# schema.net
KiCad netlist of a schematic drawn in EAGLE
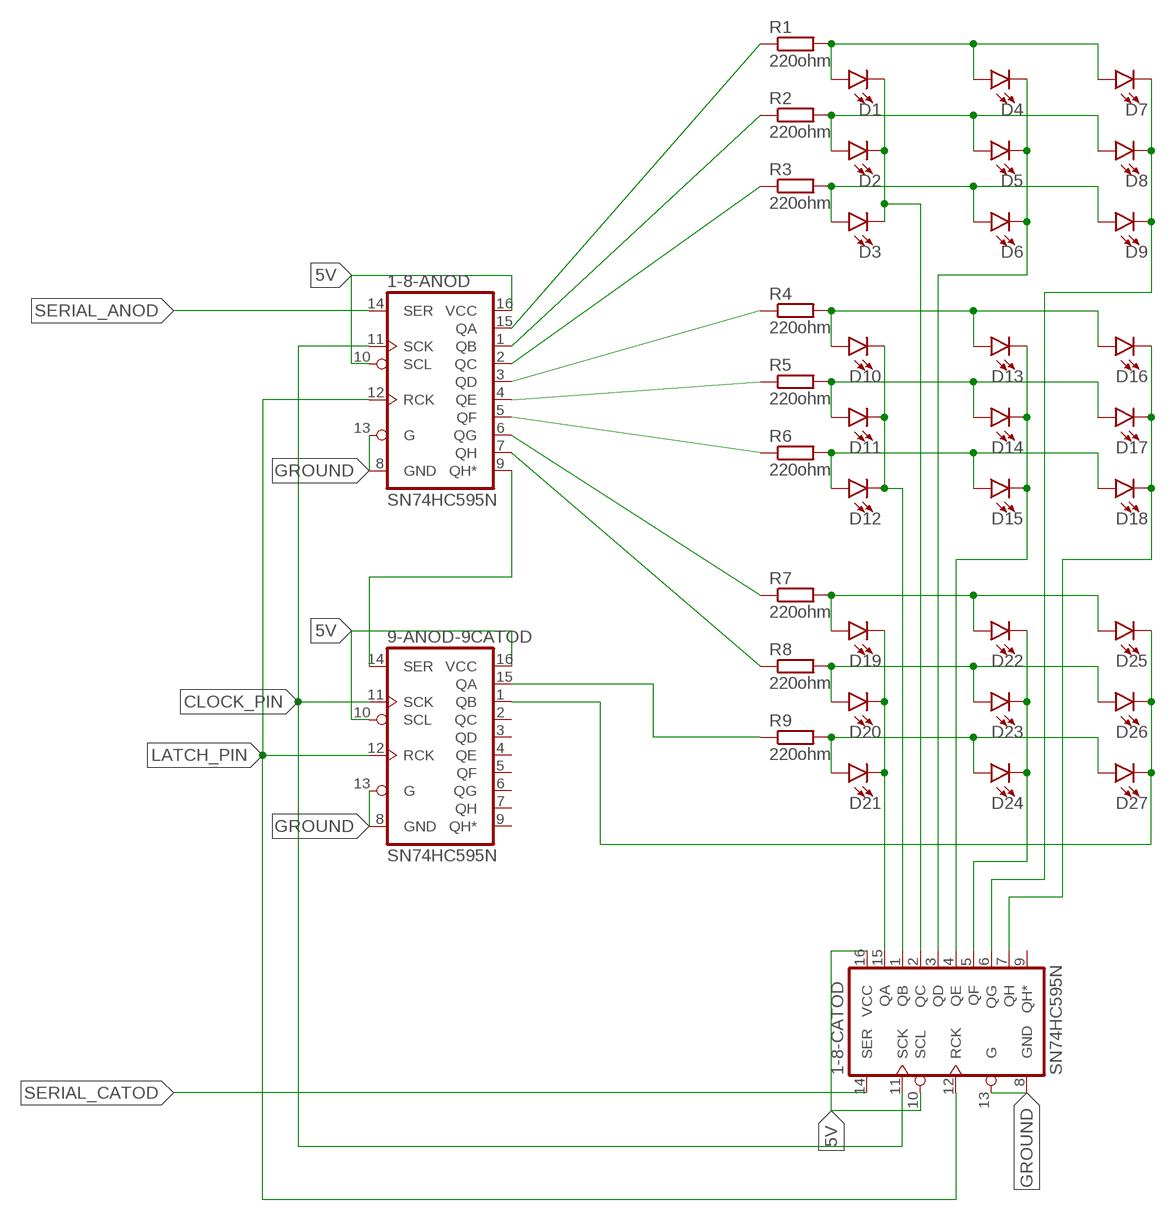
[diagram p0: schematic, sheet 1]

(export (version "E")
  (design (tool "Eeschema 10.0.6"))
  (components
    (comp (ref "1-8-ANOD")
      (value "SN74HC595N")
      (footprint "eagle-import:DIP16")
      (libsource (lib "eagle-import") (part "74595NHC"))
    )
    (comp (ref "1-8-CATOD")
      (value "SN74HC595N")
      (footprint "eagle-import:DIP16")
      (libsource (lib "eagle-import") (part "74595NHC"))
    )
    (comp (ref "9-ANOD-9CATOD")
      (value "SN74HC595N")
      (footprint "eagle-import:DIP16")
      (libsource (lib "eagle-import") (part "74595NHC"))
    )
    (comp (ref "D1")
      (value "LED5MM")
      (footprint "eagle-import:LED_5MM")
      (libsource (lib "eagle-import") (part "LED5MM"))
    )
    (comp (ref "D2")
      (value "LED5MM")
      (footprint "eagle-import:LED_5MM")
      (libsource (lib "eagle-import") (part "LED5MM"))
    )
    (comp (ref "D3")
      (value "LED5MM")
      (footprint "eagle-import:LED_5MM")
      (libsource (lib "eagle-import") (part "LED5MM"))
    )
    (comp (ref "D4")
      (value "LED5MM")
      (footprint "eagle-import:LED_5MM")
      (libsource (lib "eagle-import") (part "LED5MM"))
    )
    (comp (ref "D5")
      (value "LED5MM")
      (footprint "eagle-import:LED_5MM")
      (libsource (lib "eagle-import") (part "LED5MM"))
    )
    (comp (ref "D6")
      (value "LED5MM")
      (footprint "eagle-import:LED_5MM")
      (libsource (lib "eagle-import") (part "LED5MM"))
    )
    (comp (ref "D7")
      (value "LED5MM")
      (footprint "eagle-import:LED_5MM")
      (libsource (lib "eagle-import") (part "LED5MM"))
    )
    (comp (ref "D8")
      (value "LED5MM")
      (footprint "eagle-import:LED_5MM")
      (libsource (lib "eagle-import") (part "LED5MM"))
    )
    (comp (ref "D9")
      (value "LED5MM")
      (footprint "eagle-import:LED_5MM")
      (libsource (lib "eagle-import") (part "LED5MM"))
    )
    (comp (ref "D10")
      (value "LED5MM")
      (footprint "eagle-import:LED_5MM")
      (libsource (lib "eagle-import") (part "LED5MM"))
    )
    (comp (ref "D11")
      (value "LED5MM")
      (footprint "eagle-import:LED_5MM")
      (libsource (lib "eagle-import") (part "LED5MM"))
    )
    (comp (ref "D12")
      (value "LED5MM")
      (footprint "eagle-import:LED_5MM")
      (libsource (lib "eagle-import") (part "LED5MM"))
    )
    (comp (ref "D13")
      (value "LED5MM")
      (footprint "eagle-import:LED_5MM")
      (libsource (lib "eagle-import") (part "LED5MM"))
    )
    (comp (ref "D14")
      (value "LED5MM")
      (footprint "eagle-import:LED_5MM")
      (libsource (lib "eagle-import") (part "LED5MM"))
    )
    (comp (ref "D15")
      (value "LED5MM")
      (footprint "eagle-import:LED_5MM")
      (libsource (lib "eagle-import") (part "LED5MM"))
    )
    (comp (ref "D16")
      (value "LED5MM")
      (footprint "eagle-import:LED_5MM")
      (libsource (lib "eagle-import") (part "LED5MM"))
    )
    (comp (ref "D17")
      (value "LED5MM")
      (footprint "eagle-import:LED_5MM")
      (libsource (lib "eagle-import") (part "LED5MM"))
    )
    (comp (ref "D18")
      (value "LED5MM")
      (footprint "eagle-import:LED_5MM")
      (libsource (lib "eagle-import") (part "LED5MM"))
    )
    (comp (ref "D19")
      (value "LED5MM")
      (footprint "eagle-import:LED_5MM")
      (libsource (lib "eagle-import") (part "LED5MM"))
    )
    (comp (ref "D20")
      (value "LED5MM")
      (footprint "eagle-import:LED_5MM")
      (libsource (lib "eagle-import") (part "LED5MM"))
    )
    (comp (ref "D21")
      (value "LED5MM")
      (footprint "eagle-import:LED_5MM")
      (libsource (lib "eagle-import") (part "LED5MM"))
    )
    (comp (ref "D22")
      (value "LED5MM")
      (footprint "eagle-import:LED_5MM")
      (libsource (lib "eagle-import") (part "LED5MM"))
    )
    (comp (ref "D23")
      (value "LED5MM")
      (footprint "eagle-import:LED_5MM")
      (libsource (lib "eagle-import") (part "LED5MM"))
    )
    (comp (ref "D24")
      (value "LED5MM")
      (footprint "eagle-import:LED_5MM")
      (libsource (lib "eagle-import") (part "LED5MM"))
    )
    (comp (ref "D25")
      (value "LED5MM")
      (footprint "eagle-import:LED_5MM")
      (libsource (lib "eagle-import") (part "LED5MM"))
    )
    (comp (ref "D26")
      (value "LED5MM")
      (footprint "eagle-import:LED_5MM")
      (libsource (lib "eagle-import") (part "LED5MM"))
    )
    (comp (ref "D27")
      (value "LED5MM")
      (footprint "eagle-import:LED_5MM")
      (libsource (lib "eagle-import") (part "LED5MM"))
    )
    (comp (ref "R1")
      (value "220ohm")
      (footprint "eagle-import:0207_10")
      (libsource (lib "eagle-import") (part "R-EU_0207/10"))
    )
    (comp (ref "R2")
      (value "220ohm")
      (footprint "eagle-import:0207_10")
      (libsource (lib "eagle-import") (part "R-EU_0207/10"))
    )
    (comp (ref "R3")
      (value "220ohm")
      (footprint "eagle-import:0207_10")
      (libsource (lib "eagle-import") (part "R-EU_0207/10"))
    )
    (comp (ref "R4")
      (value "220ohm")
      (footprint "eagle-import:0207_10")
      (libsource (lib "eagle-import") (part "R-EU_0207/10"))
    )
    (comp (ref "R5")
      (value "220ohm")
      (footprint "eagle-import:0207_10")
      (libsource (lib "eagle-import") (part "R-EU_0207/10"))
    )
    (comp (ref "R6")
      (value "220ohm")
      (footprint "eagle-import:0207_10")
      (libsource (lib "eagle-import") (part "R-EU_0207/10"))
    )
    (comp (ref "R7")
      (value "220ohm")
      (footprint "eagle-import:0207_10")
      (libsource (lib "eagle-import") (part "R-EU_0207/10"))
    )
    (comp (ref "R8")
      (value "220ohm")
      (footprint "eagle-import:0207_10")
      (libsource (lib "eagle-import") (part "R-EU_0207/10"))
    )
    (comp (ref "R9")
      (value "220ohm")
      (footprint "eagle-import:0207_10")
      (libsource (lib "eagle-import") (part "R-EU_0207/10"))
    )
  )
  (nets
    (net (code "1") (name "5V") (class "Default")
      (node (ref "1-8-ANOD") (pin "10") (pinfunction "SCL_10") (pintype "input"))
      (node (ref "1-8-ANOD") (pin "16") (pinfunction "VCC_16") (pintype "power_in"))
      (node (ref "1-8-CATOD") (pin "10") (pinfunction "SCL_10") (pintype "input"))
      (node (ref "1-8-CATOD") (pin "16") (pinfunction "VCC_16") (pintype "power_in"))
      (node (ref "9-ANOD-9CATOD") (pin "10") (pinfunction "SCL_10") (pintype "input"))
      (node (ref "9-ANOD-9CATOD") (pin "16") (pinfunction "VCC_16") (pintype "power_in"))
    )
    (net (code "2") (name "CLOCK_PIN") (class "Default")
      (node (ref "1-8-ANOD") (pin "11") (pinfunction "SCK_11") (pintype "input"))
      (node (ref "1-8-CATOD") (pin "11") (pinfunction "SCK_11") (pintype "input"))
      (node (ref "9-ANOD-9CATOD") (pin "11") (pinfunction "SCK_11") (pintype "input"))
    )
    (net (code "3") (name "GROUND") (class "Default")
      (node (ref "1-8-ANOD") (pin "13") (pinfunction "G_13") (pintype "input"))
      (node (ref "1-8-ANOD") (pin "8") (pinfunction "GND_8") (pintype "power_in"))
      (node (ref "1-8-CATOD") (pin "13") (pinfunction "G_13") (pintype "input"))
      (node (ref "1-8-CATOD") (pin "8") (pinfunction "GND_8") (pintype "power_in"))
      (node (ref "9-ANOD-9CATOD") (pin "13") (pinfunction "G_13") (pintype "input"))
      (node (ref "9-ANOD-9CATOD") (pin "8") (pinfunction "GND_8") (pintype "power_in"))
    )
    (net (code "4") (name "LATCH_PIN") (class "Default")
      (node (ref "1-8-ANOD") (pin "12") (pinfunction "RCK_12") (pintype "input"))
      (node (ref "1-8-CATOD") (pin "12") (pinfunction "RCK_12") (pintype "input"))
      (node (ref "9-ANOD-9CATOD") (pin "12") (pinfunction "RCK_12") (pintype "input"))
    )
    (net (code "5") (name "Net-(1-8-ANOD-QA)") (class "Default")
      (node (ref "1-8-ANOD") (pin "15") (pinfunction "QA_15") (pintype "tri_state"))
      (node (ref "R1") (pin "1") (pinfunction "1_1") (pintype "passive"))
    )
    (net (code "6") (name "Net-(1-8-ANOD-QB)") (class "Default")
      (node (ref "1-8-ANOD") (pin "1") (pinfunction "QB_1") (pintype "tri_state"))
      (node (ref "R2") (pin "1") (pinfunction "1_1") (pintype "passive"))
    )
    (net (code "7") (name "Net-(1-8-ANOD-QC)") (class "Default")
      (node (ref "1-8-ANOD") (pin "2") (pinfunction "QC_2") (pintype "tri_state"))
      (node (ref "R3") (pin "1") (pinfunction "1_1") (pintype "passive"))
    )
    (net (code "8") (name "Net-(1-8-ANOD-QD)") (class "Default")
      (node (ref "1-8-ANOD") (pin "3") (pinfunction "QD_3") (pintype "tri_state"))
      (node (ref "R4") (pin "1") (pinfunction "1_1") (pintype "passive"))
    )
    (net (code "9") (name "Net-(1-8-ANOD-QE)") (class "Default")
      (node (ref "1-8-ANOD") (pin "4") (pinfunction "QE_4") (pintype "tri_state"))
      (node (ref "R5") (pin "1") (pinfunction "1_1") (pintype "passive"))
    )
    (net (code "10") (name "Net-(1-8-ANOD-QF)") (class "Default")
      (node (ref "1-8-ANOD") (pin "5") (pinfunction "QF_5") (pintype "tri_state"))
      (node (ref "R6") (pin "1") (pinfunction "1_1") (pintype "passive"))
    )
    (net (code "11") (name "Net-(1-8-ANOD-QG)") (class "Default")
      (node (ref "1-8-ANOD") (pin "6") (pinfunction "QG_6") (pintype "tri_state"))
      (node (ref "R7") (pin "1") (pinfunction "1_1") (pintype "passive"))
    )
    (net (code "12") (name "Net-(1-8-ANOD-QH)") (class "Default")
      (node (ref "1-8-ANOD") (pin "7") (pinfunction "QH_7") (pintype "tri_state"))
      (node (ref "R8") (pin "1") (pinfunction "1_1") (pintype "passive"))
    )
    (net (code "13") (name "Net-(1-8-ANOD-QH*)") (class "Default")
      (node (ref "1-8-ANOD") (pin "9") (pinfunction "QH*_9") (pintype "tri_state"))
      (node (ref "9-ANOD-9CATOD") (pin "14") (pinfunction "SER_14") (pintype "input"))
    )
    (net (code "14") (name "Net-(1-8-CATOD-QA)") (class "Default")
      (node (ref "1-8-CATOD") (pin "15") (pinfunction "QA_15") (pintype "tri_state"))
      (node (ref "D19") (pin "K") (pinfunction "C_K") (pintype "passive"))
      (node (ref "D20") (pin "K") (pinfunction "C_K") (pintype "passive"))
      (node (ref "D21") (pin "K") (pinfunction "C_K") (pintype "passive"))
    )
    (net (code "15") (name "Net-(1-8-CATOD-QB)") (class "Default")
      (node (ref "1-8-CATOD") (pin "1") (pinfunction "QB_1") (pintype "tri_state"))
      (node (ref "D10") (pin "K") (pinfunction "C_K") (pintype "passive"))
      (node (ref "D11") (pin "K") (pinfunction "C_K") (pintype "passive"))
      (node (ref "D12") (pin "K") (pinfunction "C_K") (pintype "passive"))
    )
    (net (code "16") (name "Net-(1-8-CATOD-QC)") (class "Default")
      (node (ref "1-8-CATOD") (pin "2") (pinfunction "QC_2") (pintype "tri_state"))
      (node (ref "D1") (pin "K") (pinfunction "C_K") (pintype "passive"))
      (node (ref "D2") (pin "K") (pinfunction "C_K") (pintype "passive"))
      (node (ref "D3") (pin "K") (pinfunction "C_K") (pintype "passive"))
    )
    (net (code "17") (name "Net-(1-8-CATOD-QD)") (class "Default")
      (node (ref "1-8-CATOD") (pin "3") (pinfunction "QD_3") (pintype "tri_state"))
      (node (ref "D4") (pin "K") (pinfunction "C_K") (pintype "passive"))
      (node (ref "D5") (pin "K") (pinfunction "C_K") (pintype "passive"))
      (node (ref "D6") (pin "K") (pinfunction "C_K") (pintype "passive"))
    )
    (net (code "18") (name "Net-(1-8-CATOD-QE)") (class "Default")
      (node (ref "1-8-CATOD") (pin "4") (pinfunction "QE_4") (pintype "tri_state"))
      (node (ref "D13") (pin "K") (pinfunction "C_K") (pintype "passive"))
      (node (ref "D14") (pin "K") (pinfunction "C_K") (pintype "passive"))
      (node (ref "D15") (pin "K") (pinfunction "C_K") (pintype "passive"))
    )
    (net (code "19") (name "Net-(1-8-CATOD-QF)") (class "Default")
      (node (ref "1-8-CATOD") (pin "5") (pinfunction "QF_5") (pintype "tri_state"))
      (node (ref "D22") (pin "K") (pinfunction "C_K") (pintype "passive"))
      (node (ref "D23") (pin "K") (pinfunction "C_K") (pintype "passive"))
      (node (ref "D24") (pin "K") (pinfunction "C_K") (pintype "passive"))
    )
    (net (code "20") (name "Net-(1-8-CATOD-QG)") (class "Default")
      (node (ref "1-8-CATOD") (pin "6") (pinfunction "QG_6") (pintype "tri_state"))
      (node (ref "D7") (pin "K") (pinfunction "C_K") (pintype "passive"))
      (node (ref "D8") (pin "K") (pinfunction "C_K") (pintype "passive"))
      (node (ref "D9") (pin "K") (pinfunction "C_K") (pintype "passive"))
    )
    (net (code "21") (name "Net-(1-8-CATOD-QH)") (class "Default")
      (node (ref "1-8-CATOD") (pin "7") (pinfunction "QH_7") (pintype "tri_state"))
      (node (ref "D16") (pin "K") (pinfunction "C_K") (pintype "passive"))
      (node (ref "D17") (pin "K") (pinfunction "C_K") (pintype "passive"))
      (node (ref "D18") (pin "K") (pinfunction "C_K") (pintype "passive"))
    )
    (net (code "22") (name "Net-(9-ANOD-9CATOD-QA)") (class "Default")
      (node (ref "9-ANOD-9CATOD") (pin "15") (pinfunction "QA_15") (pintype "tri_state"))
      (node (ref "R9") (pin "1") (pinfunction "1_1") (pintype "passive"))
    )
    (net (code "23") (name "Net-(9-ANOD-9CATOD-QB)") (class "Default")
      (node (ref "9-ANOD-9CATOD") (pin "1") (pinfunction "QB_1") (pintype "tri_state"))
      (node (ref "D25") (pin "K") (pinfunction "C_K") (pintype "passive"))
      (node (ref "D26") (pin "K") (pinfunction "C_K") (pintype "passive"))
      (node (ref "D27") (pin "K") (pinfunction "C_K") (pintype "passive"))
    )
    (net (code "24") (name "Net-(D1-PadA)") (class "Default")
      (node (ref "D1") (pin "A") (pinfunction "A_A") (pintype "passive"))
      (node (ref "D4") (pin "A") (pinfunction "A_A") (pintype "passive"))
      (node (ref "D7") (pin "A") (pinfunction "A_A") (pintype "passive"))
      (node (ref "R1") (pin "2") (pinfunction "2_2") (pintype "passive"))
    )
    (net (code "25") (name "Net-(D2-PadA)") (class "Default")
      (node (ref "D2") (pin "A") (pinfunction "A_A") (pintype "passive"))
      (node (ref "D5") (pin "A") (pinfunction "A_A") (pintype "passive"))
      (node (ref "D8") (pin "A") (pinfunction "A_A") (pintype "passive"))
      (node (ref "R2") (pin "2") (pinfunction "2_2") (pintype "passive"))
    )
    (net (code "26") (name "Net-(D3-PadA)") (class "Default")
      (node (ref "D3") (pin "A") (pinfunction "A_A") (pintype "passive"))
      (node (ref "D6") (pin "A") (pinfunction "A_A") (pintype "passive"))
      (node (ref "D9") (pin "A") (pinfunction "A_A") (pintype "passive"))
      (node (ref "R3") (pin "2") (pinfunction "2_2") (pintype "passive"))
    )
    (net (code "27") (name "Net-(D10-PadA)") (class "Default")
      (node (ref "D10") (pin "A") (pinfunction "A_A") (pintype "passive"))
      (node (ref "D13") (pin "A") (pinfunction "A_A") (pintype "passive"))
      (node (ref "D16") (pin "A") (pinfunction "A_A") (pintype "passive"))
      (node (ref "R4") (pin "2") (pinfunction "2_2") (pintype "passive"))
    )
    (net (code "28") (name "Net-(D11-PadA)") (class "Default")
      (node (ref "D11") (pin "A") (pinfunction "A_A") (pintype "passive"))
      (node (ref "D14") (pin "A") (pinfunction "A_A") (pintype "passive"))
      (node (ref "D17") (pin "A") (pinfunction "A_A") (pintype "passive"))
      (node (ref "R5") (pin "2") (pinfunction "2_2") (pintype "passive"))
    )
    (net (code "29") (name "Net-(D12-PadA)") (class "Default")
      (node (ref "D12") (pin "A") (pinfunction "A_A") (pintype "passive"))
      (node (ref "D15") (pin "A") (pinfunction "A_A") (pintype "passive"))
      (node (ref "D18") (pin "A") (pinfunction "A_A") (pintype "passive"))
      (node (ref "R6") (pin "2") (pinfunction "2_2") (pintype "passive"))
    )
    (net (code "30") (name "Net-(D19-PadA)") (class "Default")
      (node (ref "D19") (pin "A") (pinfunction "A_A") (pintype "passive"))
      (node (ref "D22") (pin "A") (pinfunction "A_A") (pintype "passive"))
      (node (ref "D25") (pin "A") (pinfunction "A_A") (pintype "passive"))
      (node (ref "R7") (pin "2") (pinfunction "2_2") (pintype "passive"))
    )
    (net (code "31") (name "Net-(D20-PadA)") (class "Default")
      (node (ref "D20") (pin "A") (pinfunction "A_A") (pintype "passive"))
      (node (ref "D23") (pin "A") (pinfunction "A_A") (pintype "passive"))
      (node (ref "D26") (pin "A") (pinfunction "A_A") (pintype "passive"))
      (node (ref "R8") (pin "2") (pinfunction "2_2") (pintype "passive"))
    )
    (net (code "32") (name "Net-(D21-PadA)") (class "Default")
      (node (ref "D21") (pin "A") (pinfunction "A_A") (pintype "passive"))
      (node (ref "D24") (pin "A") (pinfunction "A_A") (pintype "passive"))
      (node (ref "D27") (pin "A") (pinfunction "A_A") (pintype "passive"))
      (node (ref "R9") (pin "2") (pinfunction "2_2") (pintype "passive"))
    )
    (net (code "33") (name "SERIAL_ANOD") (class "Default")
      (node (ref "1-8-ANOD") (pin "14") (pinfunction "SER_14") (pintype "input"))
    )
    (net (code "34") (name "SERIAL_CATOD") (class "Default")
      (node (ref "1-8-CATOD") (pin "14") (pinfunction "SER_14") (pintype "input"))
    )
    (net (code "35") (name "unconnected-(1-8-CATOD-QH*-Pad9)") (class "Default")
      (node (ref "1-8-CATOD") (pin "9") (pinfunction "QH*_9") (pintype "tri_state"))
    )
    (net (code "36") (name "unconnected-(9-ANOD-9CATOD-QC-Pad2)") (class "Default")
      (node (ref "9-ANOD-9CATOD") (pin "2") (pinfunction "QC_2") (pintype "tri_state"))
    )
    (net (code "37") (name "unconnected-(9-ANOD-9CATOD-QD-Pad3)") (class "Default")
      (node (ref "9-ANOD-9CATOD") (pin "3") (pinfunction "QD_3") (pintype "tri_state"))
    )
    (net (code "38") (name "unconnected-(9-ANOD-9CATOD-QE-Pad4)") (class "Default")
      (node (ref "9-ANOD-9CATOD") (pin "4") (pinfunction "QE_4") (pintype "tri_state"))
    )
    (net (code "39") (name "unconnected-(9-ANOD-9CATOD-QF-Pad5)") (class "Default")
      (node (ref "9-ANOD-9CATOD") (pin "5") (pinfunction "QF_5") (pintype "tri_state"))
    )
    (net (code "40") (name "unconnected-(9-ANOD-9CATOD-QG-Pad6)") (class "Default")
      (node (ref "9-ANOD-9CATOD") (pin "6") (pinfunction "QG_6") (pintype "tri_state"))
    )
    (net (code "41") (name "unconnected-(9-ANOD-9CATOD-QH*-Pad9)") (class "Default")
      (node (ref "9-ANOD-9CATOD") (pin "9") (pinfunction "QH*_9") (pintype "tri_state"))
    )
    (net (code "42") (name "unconnected-(9-ANOD-9CATOD-QH-Pad7)") (class "Default")
      (node (ref "9-ANOD-9CATOD") (pin "7") (pinfunction "QH_7") (pintype "tri_state"))
    )
  )
)
